# Avometer_v1_1_1.net
KiCad netlist of a schematic drawn in Altium Designer
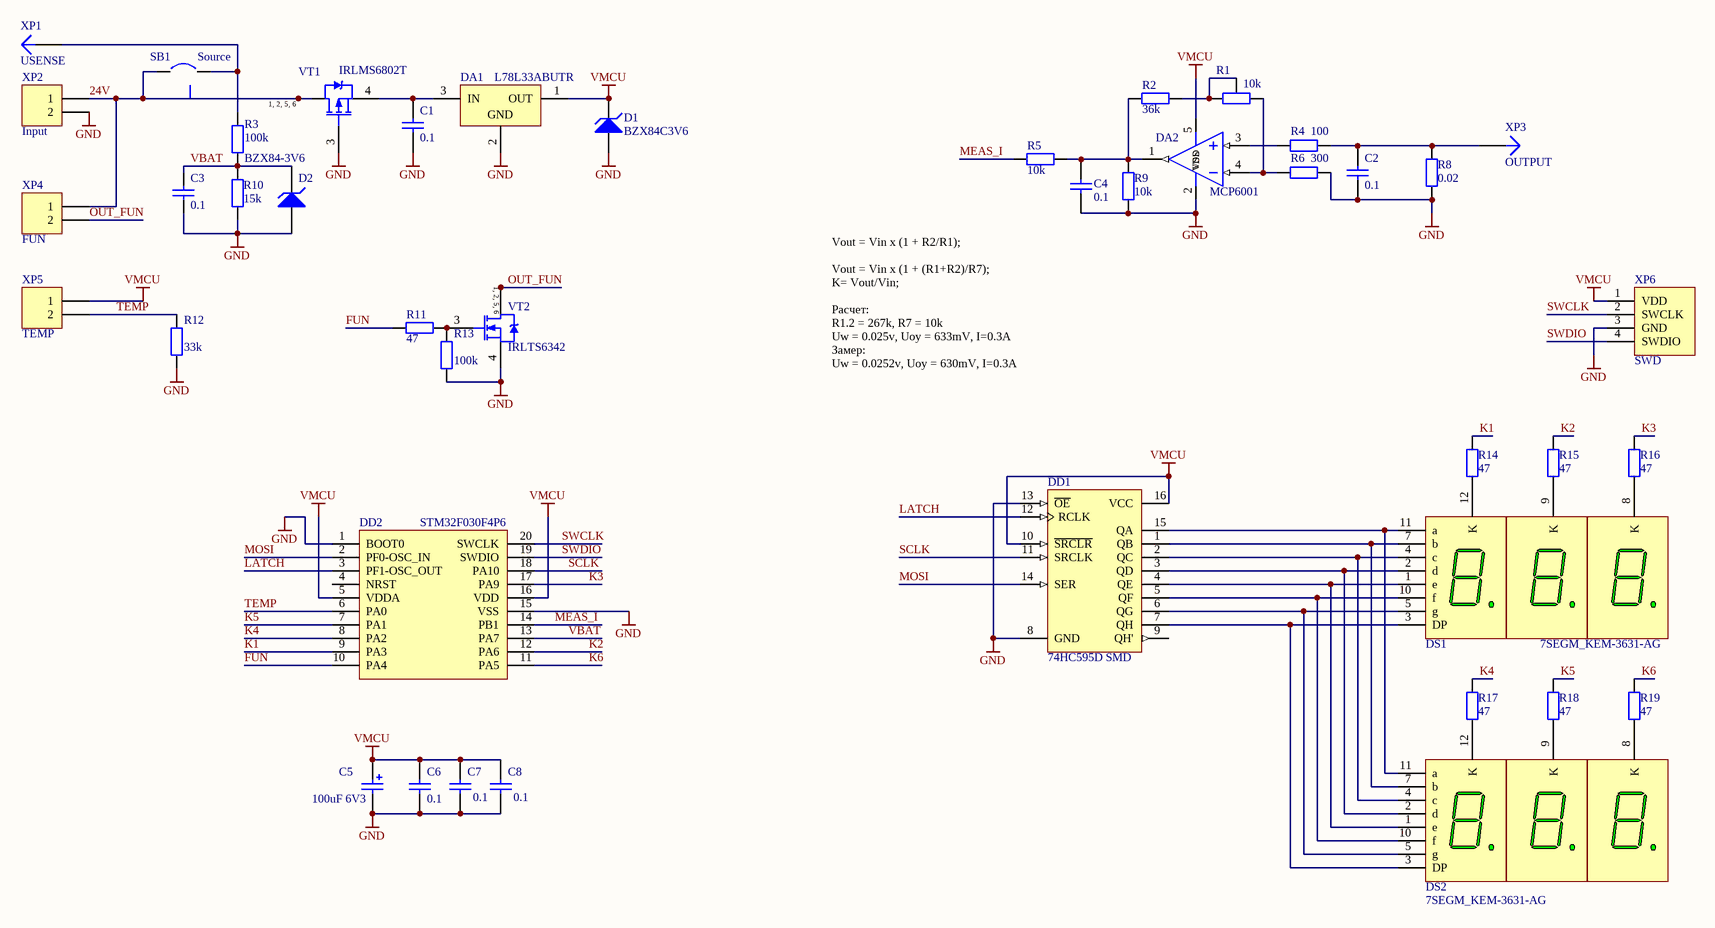
[diagram p0: Avometer v1.1.1.SchDoc]

(export (version "E")
  (design (tool "Eeschema 10.0.6"))
  (components
    (comp (ref "C1")
      (value "0.1")
      (footprint "CAP 0603_N")
      (description "Capacitor SMD")
      (libsource (lib "MyLibrary") (part "CAP_SMD"))
    )
    (comp (ref "C2")
      (value "0.1")
      (footprint "CAP 0603_N")
      (description "Capacitor SMD")
      (libsource (lib "MyLibrary") (part "CAP_SMD"))
    )
    (comp (ref "C3") (value "0.1") (footprint "CAP 0603_N") (libsource (lib "") (part "CAP_SMD_1")))
    (comp (ref "C4")
      (value "0.1")
      (footprint "CAP 0603_N")
      (description "Capacitor SMD")
      (libsource (lib "MyLibrary") (part "CAP_SMD"))
    )
    (comp (ref "C5")
      (value "100uF 6V3")
      (footprint "CAP_TANT_B_TYPE_3528-21")
      (description "Capacitor SMD Tantalum")
      (libsource (lib "MyLibrary") (part "CAP_SMD_TANT"))
    )
    (comp (ref "C6")
      (value "0.1")
      (footprint "CAP 0603_N")
      (description "Capacitor SMD")
      (libsource (lib "MyLibrary") (part "CAP_SMD"))
    )
    (comp (ref "C7")
      (value "0.1")
      (footprint "CAP 0603_N")
      (description "Capacitor SMD")
      (libsource (lib "MyLibrary") (part "CAP_SMD"))
    )
    (comp (ref "C8")
      (value "0.1")
      (footprint "CAP 0603_N")
      (description "Capacitor SMD")
      (libsource (lib "MyLibrary") (part "CAP_SMD"))
    )
    (comp (ref "D1")
      (value "BZX84C3V6")
      (footprint "SOT-23_L")
      (description "Zener Diode")
      (fields (field (name "PUBLISHER") "Altium Limited"))
      (libsource (lib "") (part "BZX84_1"))
    )
    (comp (ref "D2")
      (value "BZX84-3V6")
      (footprint "SOT-23_L")
      (description "Zener Diode")
      (fields (field (name "PUBLISHER") "Altium Limited"))
      (libsource (lib "MyLibrary") (part "BZX84"))
    )
    (comp (ref "DA1")
      (value "L78L33ABUTR")
      (footprint "SOT-89")
      (description "Vin=30V Positive Voltage Regulator")
      (fields (field (name "PUBLISHER") "Altium Limited"))
      (libsource (lib "MyLibrary") (part "L78L33ABUTR"))
    )
    (comp (ref "DA2")
      (value "MCP6001")
      (footprint "SOT-23-5_L")
      (description "1 MHz, Low-Power Op Amp")
      (libsource (lib "MyLibrary") (part "MCP6001"))
    )
    (comp (ref "DD1")
      (value "74HC595D SMD")
      (footprint "SOIC-16_L")
      (description "8-Bit Shift Register with 3-State Output Registers")
      (fields (field (name "PUBLISHER") "Altium Limited"))
      (libsource (lib "MyLibrary") (part "74HC595D SMD"))
    )
    (comp (ref "DD2")
      (value "STM32F030F4P6")
      (footprint "TSSOP-20_N")
      (description "Cortex-M0 32-bit MCU, 16 KB Flash, 4 KB Internal RAM, 15 I/Os, 20-pin TSSOP, -40 to 85 degC")
      (libsource (lib "MyLibrary") (part "STM32F030F4P6"))
    )
    (comp (ref "DS1")
      (value "7SEGM_KEM-3631-AG")
      (footprint "7SEGM_KEM-3631-AG_BLUE")
      (description "7.62 mm Black Surface Green 7-Segment Display: CC, RH DP")
      (fields (field (name "PUBLISHER") "Altium Limited"))
      (libsource (lib "MyLibrary") (part "7SEGM_KEM-3631-AG"))
    )
    (comp (ref "DS2")
      (value "7SEGM_KEM-3631-AG")
      (footprint "7SEGM_KEM-3631-AG_RED")
      (description "7.62 mm Black Surface Green 7-Segment Display: CC, RH DP")
      (fields (field (name "PUBLISHER") "Altium Limited"))
      (libsource (lib "MyLibrary") (part "7SEGM_KEM-3631-AG"))
    )
    (comp (ref "R1")
      (value "10k")
      (footprint "RES VAR 1")
      (description "Tapped Resistor")
      (fields (field (name "PUBLISHER") "Altium Limited"))
      (libsource (lib "MyLibrary") (part "RES_SMD_Tap"))
    )
    (comp (ref "R2") (value "36k") (footprint "RES 0603_N") (libsource (lib "") (part "Resistor_SMD_2")))
    (comp (ref "R3") (value "100k") (footprint "RES 0603_N") (libsource (lib "MyLibrary") (part "RES_SMD")))
    (comp (ref "R4") (value "100") (footprint "RES 0603_N") (libsource (lib "") (part "Resistor_SMD_2")))
    (comp (ref "R5")
      (value "10k")
      (footprint "RES 0603_N")
      (description "Resistor")
      (libsource (lib "") (part "RES_SMD_1"))
    )
    (comp (ref "R6") (value "300") (footprint "RES 0603_N") (libsource (lib "") (part "Resistor_SMD_2")))
    (comp (ref "R8")
      (value "0.02")
      (footprint "RES 2512")
      (description "Resistor")
      (libsource (lib "MyLibrary") (part "RES_SMD"))
    )
    (comp (ref "R9") (value "10k") (footprint "RES 0603_N") (libsource (lib "") (part "Resistor_SMD_1")))
    (comp (ref "R10") (value "15k") (footprint "RES 0603_N") (libsource (lib "MyLibrary") (part "RES_SMD")))
    (comp (ref "R11")
      (value "47")
      (footprint "RES 0603_N")
      (description "Chip Resistor")
      (libsource (lib "") (part "RES_SMD_1"))
    )
    (comp (ref "R12")
      (value "33k")
      (footprint "RES 0603_N")
      (description "Chip Resistor")
      (libsource (lib "SyntecoLibrary") (part "RES_SMD"))
    )
    (comp (ref "R13")
      (value "100k")
      (footprint "RES 0603_N")
      (description "Chip Resistor")
      (libsource (lib "SyntecoLibrary") (part "RES_SMD"))
    )
    (comp (ref "R14")
      (value "47")
      (footprint "RES 0603_N")
      (libsource (lib "MyLibrary") (part "Resistor_SMD"))
    )
    (comp (ref "R15")
      (value "47")
      (footprint "RES 0603_N")
      (libsource (lib "MyLibrary") (part "Resistor_SMD"))
    )
    (comp (ref "R16")
      (value "47")
      (footprint "RES 0603_N")
      (libsource (lib "MyLibrary") (part "Resistor_SMD"))
    )
    (comp (ref "R17")
      (value "47")
      (footprint "RES 0603_N")
      (libsource (lib "MyLibrary") (part "Resistor_SMD"))
    )
    (comp (ref "R18")
      (value "47")
      (footprint "RES 0603_N")
      (libsource (lib "MyLibrary") (part "Resistor_SMD"))
    )
    (comp (ref "R19")
      (value "47")
      (footprint "RES 0603_N")
      (libsource (lib "MyLibrary") (part "Resistor_SMD"))
    )
    (comp (ref "SB1")
      (value "Source")
      (footprint "JUMPER_SOLDERED")
      (description "Jumper")
      (libsource (lib "MyLibrary") (part "Jumper_SMD"))
    )
    (comp (ref "VT1")
      (value "IRLMS6802T")
      (footprint "SOT-23-6_L")
      (description "P-Channel MOSFET 20V 4.5A")
      (fields (field (name "PUBLISHER") "Altium Limited"))
      (libsource (lib "MyLibrary") (part "IRLMS6802T"))
    )
    (comp (ref "VT2")
      (value "IRLTS6342")
      (footprint "TSOP-6")
      (description "30V, 6.7A, 1V N-Channel MOSFET")
      (fields (field (name "PUBLISHER") "Altium Limited"))
      (libsource (lib "MyLibrary") (part "IRLTS6342"))
    )
    (comp (ref "XP1")
      (value "USENSE")
      (footprint "CON_PIN")
      (description "Plug papa")
      (fields (field (name "PUBLISHER") "Altium Limited"))
      (libsource (lib "MyLibrary") (part "CON_1x1_PIN"))
    )
    (comp (ref "XP2")
      (value "Input")
      (footprint "CON_5.08MM_1X2")
      (description "Header, 2-Pin")
      (fields (field (name "PUBLISHER") "Altium Limited"))
      (libsource (lib "MyLibrary") (part "CON_5.08mm_1x2"))
    )
    (comp (ref "XP3")
      (value "OUTPUT")
      (footprint "CON_PIN")
      (description "Plug papa")
      (fields (field (name "PUBLISHER") "Altium Limited"))
      (libsource (lib "MyLibrary") (part "CON_1x1_PIN"))
    )
    (comp (ref "XP4")
      (value "FUN")
      (footprint "CON_2.54MM_1X2")
      (description "Header, 2-Pin")
      (fields (field (name "PUBLISHER") "Altium Limited"))
      (libsource (lib "MyLibrary") (part "CON_2.54mm_1x2"))
    )
    (comp (ref "XP5")
      (value "TEMP")
      (footprint "CON_2.54MM_1X2")
      (description "Header, 2-Pin")
      (fields (field (name "PUBLISHER") "Altium Limited"))
      (libsource (lib "MyLibrary") (part "CON_2.54mm_1x2"))
    )
    (comp (ref "XP6")
      (value "SWD")
      (footprint "CON_1.27MM_1X4_SWD")
      (description "Header, 3-Pin")
      (fields (field (name "PUBLISHER") "Altium Limited"))
      (libsource (lib "MyLibrary") (part "CON_1.27mm_1x4_SWD"))
    )
  )
  (nets
    (net (code "1") (name "/24V") (class "Default")
      (node (ref "SB1") (pin "1") (pinfunction "1_1") (pintype "passive"))
      (node (ref "VT1") (pin "1") (pinfunction "D_1") (pintype "passive"))
      (node (ref "VT1") (pin "2") (pinfunction "D_2") (pintype "passive"))
      (node (ref "VT1") (pin "5") (pinfunction "D_5") (pintype "passive"))
      (node (ref "VT1") (pin "6") (pinfunction "D_6") (pintype "passive"))
      (node (ref "XP2") (pin "1") (pinfunction "1_1") (pintype "passive"))
      (node (ref "XP4") (pin "1") (pinfunction "1_1") (pintype "passive"))
    )
    (net (code "2") (name "/FUN") (class "Default")
      (node (ref "DD2") (pin "10") (pinfunction "PA4_10") (pintype "passive"))
      (node (ref "R11") (pin "2") (pinfunction "2_2") (pintype "passive"))
    )
    (net (code "3") (name "/K1") (class "Default")
      (node (ref "DD2") (pin "9") (pinfunction "PA3_9") (pintype "passive"))
      (node (ref "R14") (pin "2") (pinfunction "2_2") (pintype "passive"))
    )
    (net (code "4") (name "/K2") (class "Default")
      (node (ref "DD2") (pin "12") (pinfunction "PA6_12") (pintype "passive"))
      (node (ref "R15") (pin "2") (pinfunction "2_2") (pintype "passive"))
    )
    (net (code "5") (name "/K3") (class "Default")
      (node (ref "DD2") (pin "17") (pinfunction "PA9_17") (pintype "passive"))
      (node (ref "R16") (pin "2") (pinfunction "2_2") (pintype "passive"))
    )
    (net (code "6") (name "/K4") (class "Default")
      (node (ref "DD2") (pin "8") (pinfunction "PA2_8") (pintype "passive"))
      (node (ref "R17") (pin "2") (pinfunction "2_2") (pintype "passive"))
    )
    (net (code "7") (name "/K5") (class "Default")
      (node (ref "DD2") (pin "7") (pinfunction "PA1_7") (pintype "passive"))
      (node (ref "R18") (pin "2") (pinfunction "2_2") (pintype "passive"))
    )
    (net (code "8") (name "/K6") (class "Default")
      (node (ref "DD2") (pin "11") (pinfunction "PA5_11") (pintype "passive"))
      (node (ref "R19") (pin "2") (pinfunction "2_2") (pintype "passive"))
    )
    (net (code "9") (name "/LATCH") (class "Default")
      (node (ref "DD1") (pin "12") (pinfunction "RCLK_12") (pintype "input"))
      (node (ref "DD2") (pin "3") (pinfunction "PF1-OSC_OUT_3") (pintype "passive"))
    )
    (net (code "10") (name "/MEAS_I") (class "Default")
      (node (ref "DD2") (pin "14") (pinfunction "PB1_14") (pintype "passive"))
      (node (ref "R5") (pin "1") (pinfunction "1_1") (pintype "passive"))
    )
    (net (code "11") (name "/MOSI") (class "Default")
      (node (ref "DD1") (pin "14") (pinfunction "SER_14") (pintype "input"))
      (node (ref "DD2") (pin "2") (pinfunction "PF0-OSC_IN_2") (pintype "passive"))
    )
    (net (code "12") (name "/OUT_FUN") (class "Default")
      (node (ref "VT2") (pin "1") (pinfunction "D_1") (pintype "passive"))
      (node (ref "VT2") (pin "2") (pinfunction "D_2") (pintype "passive"))
      (node (ref "VT2") (pin "5") (pinfunction "D_5") (pintype "passive"))
      (node (ref "VT2") (pin "6") (pinfunction "D_6") (pintype "passive"))
      (node (ref "XP4") (pin "2") (pinfunction "2_2") (pintype "passive"))
    )
    (net (code "13") (name "/SCLK") (class "Default")
      (node (ref "DD1") (pin "11") (pinfunction "SRCLK_11") (pintype "input"))
      (node (ref "DD2") (pin "18") (pinfunction "PA10_18") (pintype "passive"))
    )
    (net (code "14") (name "/SWCLK") (class "Default")
      (node (ref "DD2") (pin "20") (pinfunction "SWCLK_20") (pintype "passive"))
      (node (ref "XP6") (pin "2") (pinfunction "SWCLK_2") (pintype "passive"))
    )
    (net (code "15") (name "/SWDIO") (class "Default")
      (node (ref "DD2") (pin "19") (pinfunction "SWDIO_19") (pintype "passive"))
      (node (ref "XP6") (pin "4") (pinfunction "SWDIO_4") (pintype "passive"))
    )
    (net (code "16") (name "/TEMP") (class "Default")
      (node (ref "DD2") (pin "6") (pinfunction "PA0_6") (pintype "passive"))
      (node (ref "R12") (pin "2") (pinfunction "2_2") (pintype "passive"))
      (node (ref "XP5") (pin "2") (pinfunction "2_2") (pintype "passive"))
    )
    (net (code "17") (name "/VBAT") (class "Default")
      (node (ref "C3") (pin "2") (pinfunction "2_2") (pintype "passive"))
      (node (ref "D2") (pin "3") (pinfunction "K_3") (pintype "passive"))
      (node (ref "DD2") (pin "13") (pinfunction "PA7_13") (pintype "passive"))
      (node (ref "R10") (pin "2") (pinfunction "2_2") (pintype "passive"))
      (node (ref "R3") (pin "1") (pinfunction "1_1") (pintype "passive"))
    )
    (net (code "18") (name "GND") (class "Default")
      (node (ref "C1") (pin "1") (pinfunction "1_1") (pintype "passive"))
      (node (ref "C2") (pin "1") (pinfunction "1_1") (pintype "passive"))
      (node (ref "C3") (pin "1") (pinfunction "1_1") (pintype "passive"))
      (node (ref "C4") (pin "1") (pinfunction "1_1") (pintype "passive"))
      (node (ref "C5") (pin "2") (pinfunction "2_2") (pintype "passive"))
      (node (ref "C6") (pin "1") (pinfunction "1_1") (pintype "passive"))
      (node (ref "C7") (pin "2") (pinfunction "2_2") (pintype "passive"))
      (node (ref "C8") (pin "2") (pinfunction "2_2") (pintype "passive"))
      (node (ref "D1") (pin "1") (pinfunction "A_1") (pintype "passive"))
      (node (ref "D2") (pin "1") (pinfunction "A_1") (pintype "passive"))
      (node (ref "DA1") (pin "2") (pinfunction "GND_2") (pintype "power_in"))
      (node (ref "DA2") (pin "2") (pinfunction "VSS_2") (pintype "power_in"))
      (node (ref "DD1") (pin "13") (pinfunction "~{OE}_13") (pintype "input"))
      (node (ref "DD1") (pin "8") (pinfunction "GND_8") (pintype "power_in"))
      (node (ref "DD2") (pin "1") (pinfunction "BOOT0_1") (pintype "passive"))
      (node (ref "DD2") (pin "15") (pinfunction "VSS_15") (pintype "passive"))
      (node (ref "R10") (pin "1") (pinfunction "1_1") (pintype "passive"))
      (node (ref "R12") (pin "1") (pinfunction "1_1") (pintype "passive"))
      (node (ref "R13") (pin "1") (pinfunction "1_1") (pintype "passive"))
      (node (ref "R6") (pin "1") (pinfunction "1_1") (pintype "passive"))
      (node (ref "R8") (pin "1") (pinfunction "1_1") (pintype "passive"))
      (node (ref "R9") (pin "1") (pinfunction "1_1") (pintype "passive"))
      (node (ref "VT1") (pin "3") (pinfunction "G_3") (pintype "passive"))
      (node (ref "VT2") (pin "4") (pinfunction "S_4") (pintype "passive"))
      (node (ref "XP2") (pin "2") (pinfunction "2_2") (pintype "passive"))
      (node (ref "XP6") (pin "3") (pinfunction "GND_3") (pintype "passive"))
    )
    (net (code "19") (name "Net-(C2-Pad2)") (class "Default")
      (node (ref "C2") (pin "2") (pinfunction "2_2") (pintype "passive"))
      (node (ref "R4") (pin "1") (pinfunction "1_1") (pintype "passive"))
      (node (ref "R8") (pin "2") (pinfunction "2_2") (pintype "passive"))
      (node (ref "XP3") (pin "1") (pinfunction "1_1") (pintype "passive"))
    )
    (net (code "20") (name "Net-(DA1-IN)") (class "Default")
      (node (ref "C1") (pin "2") (pinfunction "2_2") (pintype "passive"))
      (node (ref "DA1") (pin "3") (pinfunction "IN_3") (pintype "power_in"))
      (node (ref "VT1") (pin "4") (pinfunction "S_4") (pintype "passive"))
    )
    (net (code "21") (name "Net-(DA2-VIN+)") (class "Default")
      (node (ref "DA2") (pin "3") (pinfunction "VIN+_3") (pintype "input"))
      (node (ref "R4") (pin "2") (pinfunction "2_2") (pintype "passive"))
    )
    (net (code "22") (name "Net-(DA2-VIN-)") (class "Default")
      (node (ref "DA2") (pin "4") (pinfunction "VIN-_4") (pintype "input"))
      (node (ref "R1") (pin "3") (pinfunction "B_3") (pintype "passive"))
      (node (ref "R6") (pin "2") (pinfunction "2_2") (pintype "passive"))
    )
    (net (code "23") (name "Net-(DA2-VOUT)") (class "Default")
      (node (ref "C4") (pin "2") (pinfunction "2_2") (pintype "passive"))
      (node (ref "DA2") (pin "1") (pinfunction "VOUT_1") (pintype "output"))
      (node (ref "R2") (pin "2") (pinfunction "2_2") (pintype "passive"))
      (node (ref "R5") (pin "2") (pinfunction "2_2") (pintype "passive"))
      (node (ref "R9") (pin "2") (pinfunction "2_2") (pintype "passive"))
    )
    (net (code "24") (name "Net-(DD1-QA)") (class "Default")
      (node (ref "DD1") (pin "15") (pinfunction "QA_15") (pintype "tri_state"))
      (node (ref "DS1") (pin "11") (pinfunction "a_11") (pintype "passive"))
      (node (ref "DS2") (pin "11") (pinfunction "a_11") (pintype "passive"))
    )
    (net (code "25") (name "Net-(DD1-QB)") (class "Default")
      (node (ref "DD1") (pin "1") (pinfunction "QB_1") (pintype "tri_state"))
      (node (ref "DS1") (pin "7") (pinfunction "b_7") (pintype "passive"))
      (node (ref "DS2") (pin "7") (pinfunction "b_7") (pintype "passive"))
    )
    (net (code "26") (name "Net-(DD1-QC)") (class "Default")
      (node (ref "DD1") (pin "2") (pinfunction "QC_2") (pintype "tri_state"))
      (node (ref "DS1") (pin "4") (pinfunction "c_4") (pintype "passive"))
      (node (ref "DS2") (pin "4") (pinfunction "c_4") (pintype "passive"))
    )
    (net (code "27") (name "Net-(DD1-QD)") (class "Default")
      (node (ref "DD1") (pin "3") (pinfunction "QD_3") (pintype "tri_state"))
      (node (ref "DS1") (pin "2") (pinfunction "d_2") (pintype "passive"))
      (node (ref "DS2") (pin "2") (pinfunction "d_2") (pintype "passive"))
    )
    (net (code "28") (name "Net-(DD1-QE)") (class "Default")
      (node (ref "DD1") (pin "4") (pinfunction "QE_4") (pintype "tri_state"))
      (node (ref "DS1") (pin "1") (pinfunction "e_1") (pintype "passive"))
      (node (ref "DS2") (pin "1") (pinfunction "e_1") (pintype "passive"))
    )
    (net (code "29") (name "Net-(DD1-QF)") (class "Default")
      (node (ref "DD1") (pin "5") (pinfunction "QF_5") (pintype "tri_state"))
      (node (ref "DS1") (pin "10") (pinfunction "f_10") (pintype "passive"))
      (node (ref "DS2") (pin "10") (pinfunction "f_10") (pintype "passive"))
    )
    (net (code "30") (name "Net-(DD1-QG)") (class "Default")
      (node (ref "DD1") (pin "6") (pinfunction "QG_6") (pintype "tri_state"))
      (node (ref "DS1") (pin "5") (pinfunction "g_5") (pintype "passive"))
      (node (ref "DS2") (pin "5") (pinfunction "g_5") (pintype "passive"))
    )
    (net (code "31") (name "Net-(DD1-QH)") (class "Default")
      (node (ref "DD1") (pin "7") (pinfunction "QH_7") (pintype "tri_state"))
      (node (ref "DS1") (pin "3") (pinfunction "DP_3") (pintype "passive"))
      (node (ref "DS2") (pin "3") (pinfunction "DP_3") (pintype "passive"))
    )
    (net (code "32") (name "Net-(DS1-K-Pad8)") (class "Default")
      (node (ref "DS1") (pin "8") (pinfunction "K_8") (pintype "passive"))
      (node (ref "R16") (pin "1") (pinfunction "1_1") (pintype "passive"))
    )
    (net (code "33") (name "Net-(DS1-K-Pad9)") (class "Default")
      (node (ref "DS1") (pin "9") (pinfunction "K_9") (pintype "passive"))
      (node (ref "R15") (pin "1") (pinfunction "1_1") (pintype "passive"))
    )
    (net (code "34") (name "Net-(DS1-K-Pad12)") (class "Default")
      (node (ref "DS1") (pin "12") (pinfunction "K_12") (pintype "passive"))
      (node (ref "R14") (pin "1") (pinfunction "1_1") (pintype "passive"))
    )
    (net (code "35") (name "Net-(DS2-K-Pad8)") (class "Default")
      (node (ref "DS2") (pin "8") (pinfunction "K_8") (pintype "passive"))
      (node (ref "R19") (pin "1") (pinfunction "1_1") (pintype "passive"))
    )
    (net (code "36") (name "Net-(DS2-K-Pad9)") (class "Default")
      (node (ref "DS2") (pin "9") (pinfunction "K_9") (pintype "passive"))
      (node (ref "R18") (pin "1") (pinfunction "1_1") (pintype "passive"))
    )
    (net (code "37") (name "Net-(DS2-K-Pad12)") (class "Default")
      (node (ref "DS2") (pin "12") (pinfunction "K_12") (pintype "passive"))
      (node (ref "R17") (pin "1") (pinfunction "1_1") (pintype "passive"))
    )
    (net (code "38") (name "Net-(R1-A)") (class "Default")
      (node (ref "R1") (pin "1") (pinfunction "A_1") (pintype "passive"))
      (node (ref "R1") (pin "2") (pinfunction "TAP_2") (pintype "passive"))
      (node (ref "R2") (pin "1") (pinfunction "1_1") (pintype "passive"))
    )
    (net (code "39") (name "Net-(R3-Pad2)") (class "Default")
      (node (ref "R3") (pin "2") (pinfunction "2_2") (pintype "passive"))
      (node (ref "SB1") (pin "2") (pinfunction "2_2") (pintype "passive"))
      (node (ref "XP1") (pin "1") (pinfunction "1_1") (pintype "passive"))
    )
    (net (code "40") (name "Net-(VT2-G)") (class "Default")
      (node (ref "R11") (pin "1") (pinfunction "1_1") (pintype "passive"))
      (node (ref "R13") (pin "2") (pinfunction "2_2") (pintype "passive"))
      (node (ref "VT2") (pin "3") (pinfunction "G_3") (pintype "passive"))
    )
    (net (code "41") (name "VMCU") (class "Default")
      (node (ref "C5") (pin "1") (pinfunction "1_1") (pintype "passive"))
      (node (ref "C6") (pin "2") (pinfunction "2_2") (pintype "passive"))
      (node (ref "C7") (pin "1") (pinfunction "1_1") (pintype "passive"))
      (node (ref "C8") (pin "1") (pinfunction "1_1") (pintype "passive"))
      (node (ref "D1") (pin "3") (pinfunction "K_3") (pintype "passive"))
      (node (ref "DA1") (pin "1") (pinfunction "OUT_1") (pintype "power_in"))
      (node (ref "DA2") (pin "5") (pinfunction "VDD_5") (pintype "power_in"))
      (node (ref "DD1") (pin "10") (pinfunction "~{SRCLR}_10") (pintype "input"))
      (node (ref "DD1") (pin "16") (pinfunction "VCC_16") (pintype "power_in"))
      (node (ref "DD2") (pin "16") (pinfunction "VDD_16") (pintype "passive"))
      (node (ref "DD2") (pin "5") (pinfunction "VDDA_5") (pintype "passive"))
      (node (ref "XP5") (pin "1") (pinfunction "1_1") (pintype "passive"))
      (node (ref "XP6") (pin "1") (pinfunction "VDD_1") (pintype "passive"))
    )
    (net (code "42") (name "unconnected-(DD1-QH'-Pad9)") (class "Default")
      (node (ref "DD1") (pin "9") (pinfunction "QH'_9") (pintype "output"))
    )
    (net (code "43") (name "unconnected-(DD2-NRST-Pad4)") (class "Default")
      (node (ref "DD2") (pin "4") (pinfunction "NRST_4") (pintype "passive"))
    )
  )
)
